# PWM_Controller_SG3525.net
KiCad netlist of a schematic drawn in Altium Designer
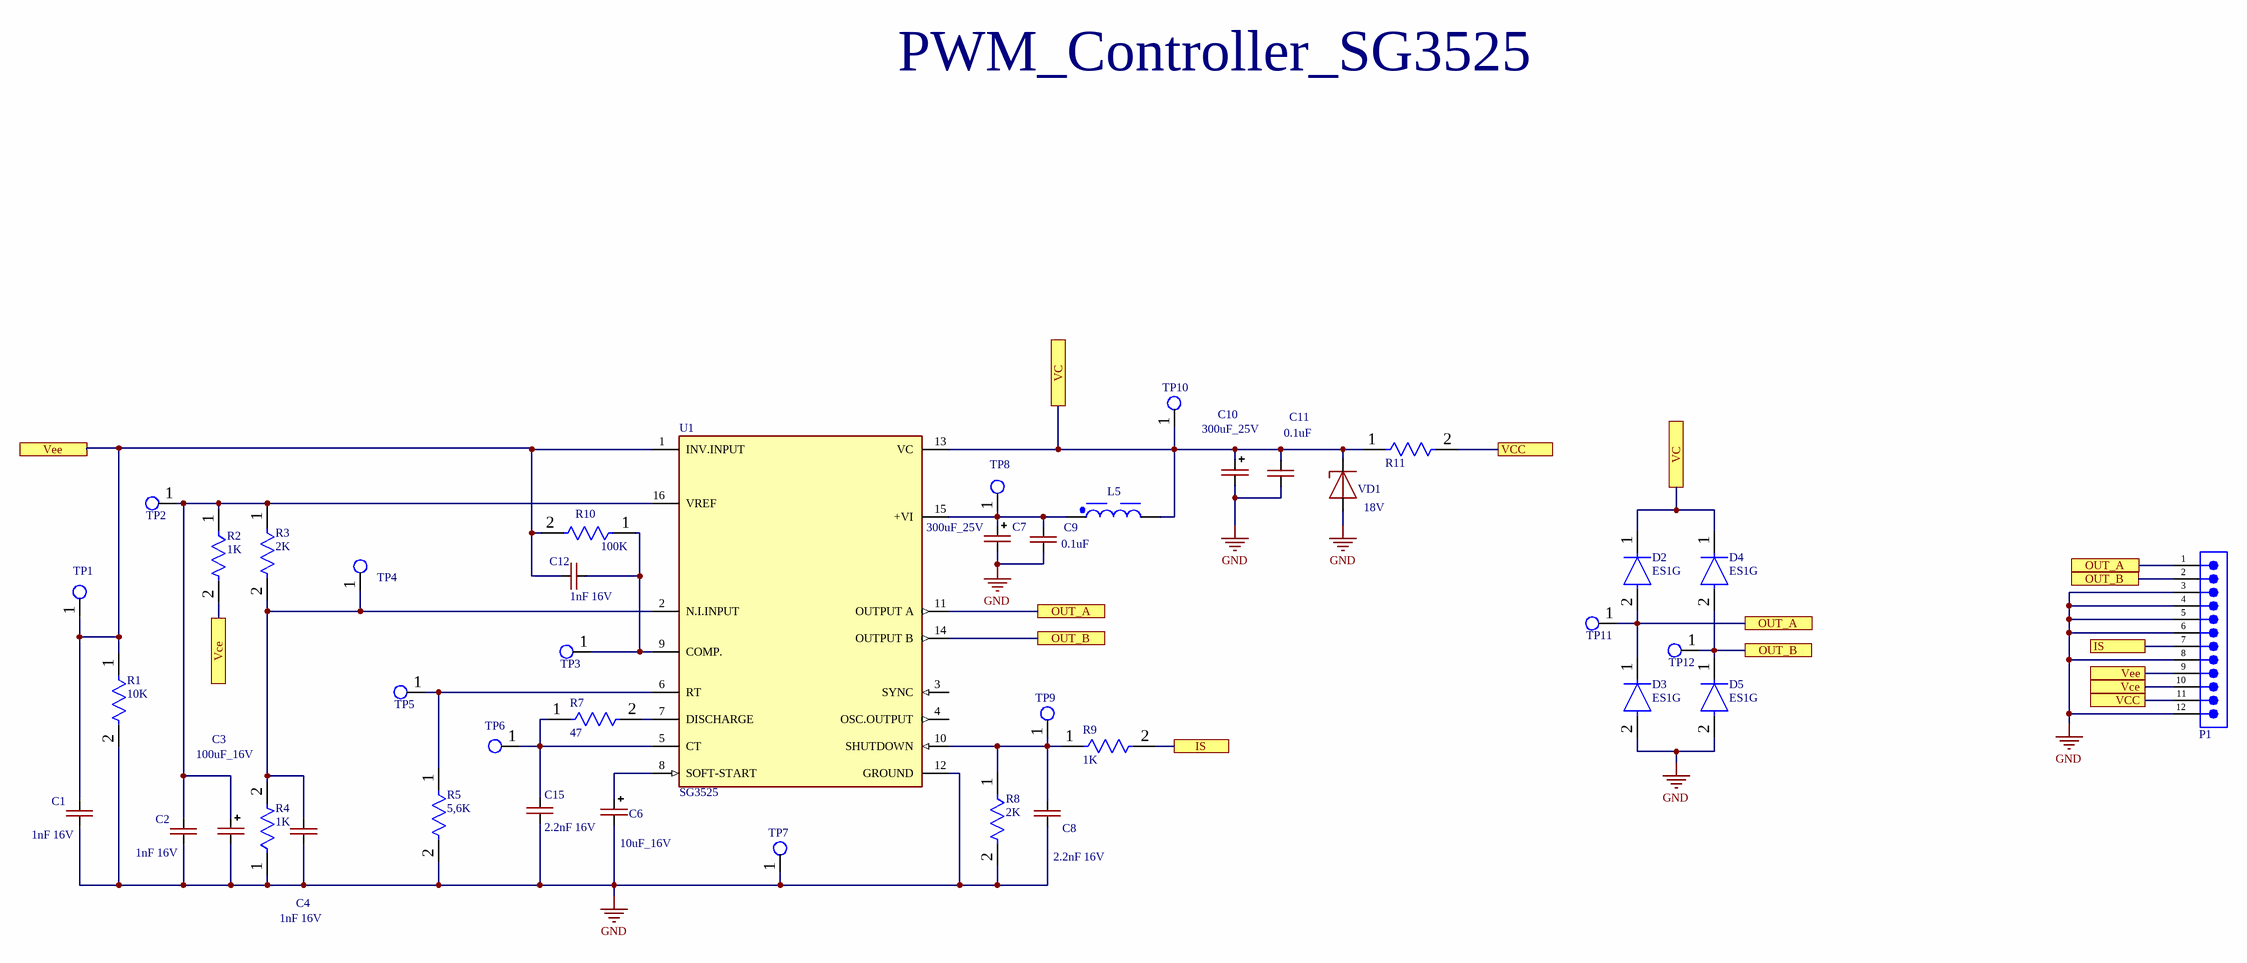
[diagram p0: PWM_Controller_SG3525.SchDoc]

(export (version "E")
  (design (tool "Eeschema 10.0.6"))
  (components
    (comp (ref "C1")
      (value "1nF 16V")
      (footprint "CAP-0805")
      (libsource (lib "PASSIVE_COMPONENTS") (part "CAP-NON-POLAR"))
    )
    (comp (ref "C2")
      (value "1nF 16V")
      (footprint "CAP-0805")
      (libsource (lib "PASSIVE_COMPONENTS") (part "CAP-NON-POLAR"))
    )
    (comp (ref "C3")
      (value "100uF_16V")
      (footprint "CAP-TAN-D")
      (libsource (lib "PASSIVE_COMPONENTS") (part "CAP-POLAR"))
    )
    (comp (ref "C4")
      (value "1nF 16V")
      (footprint "CAP-0805")
      (libsource (lib "PASSIVE_COMPONENTS") (part "CAP-NON-POLAR"))
    )
    (comp (ref "C6")
      (value "10uF_16V")
      (footprint "CAP-TAN-D")
      (libsource (lib "PASSIVE_COMPONENTS") (part "CAP-POLAR"))
    )
    (comp (ref "C7")
      (value "300uF_25V")
      (footprint "CAP_SMD_Size_G")
      (libsource (lib "PASSIVE_COMPONENTS") (part "CAP_POL_SMD"))
    )
    (comp (ref "C8")
      (value "2.2nF 16V")
      (footprint "CAP-0805")
      (libsource (lib "PASSIVE_COMPONENTS") (part "CAP-NON-POLAR"))
    )
    (comp (ref "C9")
      (value "0.1uF")
      (footprint "CAP-0805")
      (libsource (lib "PASSIVE_COMPONENTS") (part "CAP-NON-POLAR"))
    )
    (comp (ref "C10")
      (value "300uF_25V")
      (footprint "CAP_SMD_Size_G")
      (libsource (lib "PASSIVE_COMPONENTS") (part "CAP_POL_SMD"))
    )
    (comp (ref "C11")
      (value "0.1uF")
      (footprint "CAP-0805")
      (libsource (lib "PASSIVE_COMPONENTS") (part "CAP-NON-POLAR"))
    )
    (comp (ref "C12")
      (value "1nF 16V")
      (footprint "CAP-0805")
      (libsource (lib "PASSIVE_COMPONENTS") (part "CAP-NON-POLAR"))
    )
    (comp (ref "C15")
      (value "2.2nF 16V")
      (footprint "CAP-0805")
      (libsource (lib "PASSIVE_COMPONENTS") (part "CAP-NON-POLAR"))
    )
    (comp (ref "D2")
      (value "ES1G")
      (footprint "FP-403AE-MFG")
      (description "Ultrafast")
      (libsource (lib "Diodes") (part "ES1G"))
    )
    (comp (ref "D3")
      (value "ES1G")
      (footprint "FP-403AE-MFG")
      (description "Ultrafast")
      (libsource (lib "Diodes") (part "ES1G"))
    )
    (comp (ref "D4")
      (value "ES1G")
      (footprint "FP-403AE-MFG")
      (description "Ultrafast")
      (libsource (lib "Diodes") (part "ES1G"))
    )
    (comp (ref "D5")
      (value "ES1G")
      (footprint "FP-403AE-MFG")
      (description "Ultrafast")
      (libsource (lib "Diodes") (part "ES1G"))
    )
    (comp (ref "L5")
      (value "47µH, 1.17A")
      (footprint "WE-PD2_7850")
      (description "WE-PD2 SMT Power Inductor, size 7850, 47µH, 1.17A, 0.18Ω")
      (fields
        (field (name "MANUFACTURER PART NUMBER") "744775147")
        (field (name "MANUFACTURER") "Wurth Elektronik")
      )
      (libsource (lib "WE-PD2 (rev22d)") (part "744775147"))
    )
    (comp (ref "P1")
      (value "61301211021")
      (footprint "61301211021")
      (description "WR-PHD Pin Header, THT, Angled, pitch 2.54mm, 1 Row, 12P")
      (fields (field (name "MANUFACTURER") "Wurth Elektronik"))
      (libsource (lib "Altium_WR-PHD (rev22b)") (part "61301211021"))
    )
    (comp (ref "R1")
      (value "10K")
      (footprint "RES-0805")
      (libsource (lib "PASSIVE_COMPONENTS") (part "RES-CONST"))
    )
    (comp (ref "R2")
      (value "1K")
      (footprint "RES-0805")
      (libsource (lib "PASSIVE_COMPONENTS") (part "RES-CONST"))
    )
    (comp (ref "R3")
      (value "2K")
      (footprint "RES-0805")
      (libsource (lib "PASSIVE_COMPONENTS") (part "RES-CONST"))
    )
    (comp (ref "R4")
      (value "1K")
      (footprint "RES-0805")
      (libsource (lib "PASSIVE_COMPONENTS") (part "RES-CONST"))
    )
    (comp (ref "R5")
      (value "5,6K")
      (footprint "RES-0805")
      (libsource (lib "PASSIVE_COMPONENTS") (part "RES-CONST"))
    )
    (comp (ref "R7")
      (value "47")
      (footprint "RES-0805")
      (libsource (lib "PASSIVE_COMPONENTS") (part "RES-CONST"))
    )
    (comp (ref "R8")
      (value "2K")
      (footprint "RES-0805")
      (libsource (lib "PASSIVE_COMPONENTS") (part "RES-CONST"))
    )
    (comp (ref "R9")
      (value "1K")
      (footprint "RES-0805")
      (libsource (lib "PASSIVE_COMPONENTS") (part "RES-CONST"))
    )
    (comp (ref "R10")
      (value "100K")
      (footprint "RES-0805")
      (libsource (lib "PASSIVE_COMPONENTS") (part "RES-CONST"))
    )
    (comp (ref "R11")
      (value "RES_1210")
      (footprint "RES_SMD_1210_IPC_A")
      (libsource (lib "PASSIVE_COMPONENTS") (part "RES_1210"))
    )
    (comp (ref "TP1")
      (value "~")
      (footprint "Test_Point")
      (description "Test_Point")
      (libsource (lib "Connectors") (part "TP_PCB?"))
    )
    (comp (ref "TP2")
      (value "~")
      (footprint "Test_Point")
      (description "Test_Point")
      (libsource (lib "Connectors") (part "TP_PCB?"))
    )
    (comp (ref "TP3")
      (value "~")
      (footprint "Test_Point")
      (description "Test_Point")
      (libsource (lib "Connectors") (part "TP_PCB?"))
    )
    (comp (ref "TP4")
      (value "~")
      (footprint "Test_Point")
      (description "Test_Point")
      (libsource (lib "Connectors") (part "TP_PCB?"))
    )
    (comp (ref "TP5")
      (value "~")
      (footprint "Test_Point")
      (description "Test_Point")
      (libsource (lib "Connectors") (part "TP_PCB?"))
    )
    (comp (ref "TP6")
      (value "~")
      (footprint "Test_Point")
      (description "Test_Point")
      (libsource (lib "Connectors") (part "TP_PCB?"))
    )
    (comp (ref "TP7")
      (value "~")
      (footprint "Test_Point")
      (description "Test_Point")
      (libsource (lib "Connectors") (part "TP_PCB?"))
    )
    (comp (ref "TP8")
      (value "~")
      (footprint "Test_Point")
      (description "Test_Point")
      (libsource (lib "Connectors") (part "TP_PCB?"))
    )
    (comp (ref "TP9")
      (value "~")
      (footprint "Test_Point")
      (description "Test_Point")
      (libsource (lib "Connectors") (part "TP_PCB?"))
    )
    (comp (ref "TP10")
      (value "~")
      (footprint "Test_Point")
      (description "Test_Point")
      (libsource (lib "Connectors") (part "TP_PCB?"))
    )
    (comp (ref "TP11")
      (value "~")
      (footprint "Test_Point")
      (description "Test_Point")
      (libsource (lib "Connectors") (part "TP_PCB?"))
    )
    (comp (ref "TP12")
      (value "~")
      (footprint "Test_Point")
      (description "Test_Point")
      (libsource (lib "Connectors") (part "TP_PCB?"))
    )
    (comp (ref "U1")
      (value "SG3525")
      (footprint "SOIC-16-L")
      (libsource (lib "Integrated_Circuts") (part "SG3525"))
    )
    (comp (ref "VD1") (value "18V") (footprint "DO-017AA") (libsource (lib "Diodes") (part "ZENER")))
  )
  (nets
    (net (code "1") (name "/IS") (class "Default")
      (node (ref "P1") (pin "7") (pinfunction "7_7") (pintype "passive"))
      (node (ref "R9") (pin "2") (pinfunction "2_2") (pintype "passive"))
    )
    (net (code "2") (name "/OUT_A") (class "Default")
      (node (ref "D2") (pin "2") (pinfunction "A_2") (pintype "passive"))
      (node (ref "D3") (pin "1") (pinfunction "C_1") (pintype "passive"))
      (node (ref "P1") (pin "1") (pinfunction "1_1") (pintype "passive"))
      (node (ref "TP11") (pin "1") (pinfunction "G9_1") (pintype "passive"))
      (node (ref "U1") (pin "11") (pinfunction "OUTPUT_A_11") (pintype "output"))
    )
    (net (code "3") (name "/OUT_B") (class "Default")
      (node (ref "D4") (pin "2") (pinfunction "A_2") (pintype "passive"))
      (node (ref "D5") (pin "1") (pinfunction "C_1") (pintype "passive"))
      (node (ref "P1") (pin "2") (pinfunction "2_2") (pintype "passive"))
      (node (ref "TP12") (pin "1") (pinfunction "G9_1") (pintype "passive"))
      (node (ref "U1") (pin "14") (pinfunction "OUTPUT_B_14") (pintype "output"))
    )
    (net (code "4") (name "/VC") (class "Default")
      (node (ref "C10") (pin "1") (pinfunction "+_1") (pintype "passive"))
      (node (ref "C11") (pin "2") (pinfunction "2_2") (pintype "passive"))
      (node (ref "D2") (pin "1") (pinfunction "C_1") (pintype "passive"))
      (node (ref "D4") (pin "1") (pinfunction "C_1") (pintype "passive"))
      (node (ref "L5") (pin "2") (pinfunction "2_2") (pintype "passive"))
      (node (ref "R11") (pin "1") (pinfunction "1_1") (pintype "passive"))
      (node (ref "TP10") (pin "1") (pinfunction "G9_1") (pintype "passive"))
      (node (ref "U1") (pin "13") (pinfunction "VC_13") (pintype "power_in"))
      (node (ref "VD1") (pin "1") (pinfunction "C_1") (pintype "passive"))
    )
    (net (code "5") (name "/VCC") (class "Default")
      (node (ref "P1") (pin "11") (pinfunction "11_11") (pintype "passive"))
      (node (ref "R11") (pin "2") (pinfunction "2_2") (pintype "passive"))
    )
    (net (code "6") (name "/Vce") (class "Default")
      (node (ref "P1") (pin "10") (pinfunction "10_10") (pintype "passive"))
      (node (ref "R2") (pin "2") (pinfunction "2_2") (pintype "passive"))
    )
    (net (code "7") (name "/Vee") (class "Default")
      (node (ref "C1") (pin "2") (pinfunction "2_2") (pintype "passive"))
      (node (ref "C12") (pin "1") (pinfunction "1_1") (pintype "passive"))
      (node (ref "P1") (pin "9") (pinfunction "9_9") (pintype "passive"))
      (node (ref "R1") (pin "1") (pinfunction "1_1") (pintype "passive"))
      (node (ref "R10") (pin "2") (pinfunction "2_2") (pintype "passive"))
      (node (ref "TP1") (pin "1") (pinfunction "G9_1") (pintype "passive"))
      (node (ref "U1") (pin "1") (pinfunction "INV.INPUT_1") (pintype "tri_state"))
    )
    (net (code "8") (name "GND") (class "Default")
      (node (ref "C1") (pin "1") (pinfunction "1_1") (pintype "passive"))
      (node (ref "C10") (pin "2") (pinfunction "-_2") (pintype "passive"))
      (node (ref "C11") (pin "1") (pinfunction "1_1") (pintype "passive"))
      (node (ref "C15") (pin "1") (pinfunction "1_1") (pintype "passive"))
      (node (ref "C2") (pin "1") (pinfunction "1_1") (pintype "passive"))
      (node (ref "C3") (pin "2") (pinfunction "-_2") (pintype "passive"))
      (node (ref "C4") (pin "1") (pinfunction "1_1") (pintype "passive"))
      (node (ref "C6") (pin "2") (pinfunction "-_2") (pintype "passive"))
      (node (ref "C7") (pin "2") (pinfunction "-_2") (pintype "passive"))
      (node (ref "C8") (pin "1") (pinfunction "1_1") (pintype "passive"))
      (node (ref "C9") (pin "1") (pinfunction "1_1") (pintype "passive"))
      (node (ref "D3") (pin "2") (pinfunction "A_2") (pintype "passive"))
      (node (ref "D5") (pin "2") (pinfunction "A_2") (pintype "passive"))
      (node (ref "P1") (pin "12") (pinfunction "12_12") (pintype "passive"))
      (node (ref "P1") (pin "3") (pinfunction "3_3") (pintype "passive"))
      (node (ref "P1") (pin "4") (pinfunction "4_4") (pintype "passive"))
      (node (ref "P1") (pin "5") (pinfunction "5_5") (pintype "passive"))
      (node (ref "P1") (pin "6") (pinfunction "6_6") (pintype "passive"))
      (node (ref "P1") (pin "8") (pinfunction "8_8") (pintype "passive"))
      (node (ref "R1") (pin "2") (pinfunction "2_2") (pintype "passive"))
      (node (ref "R4") (pin "1") (pinfunction "1_1") (pintype "passive"))
      (node (ref "R5") (pin "2") (pinfunction "2_2") (pintype "passive"))
      (node (ref "R8") (pin "2") (pinfunction "2_2") (pintype "passive"))
      (node (ref "TP7") (pin "1") (pinfunction "G9_1") (pintype "passive"))
      (node (ref "U1") (pin "12") (pinfunction "GROUND_12") (pintype "power_in"))
      (node (ref "VD1") (pin "2") (pinfunction "A_2") (pintype "passive"))
    )
    (net (code "9") (name "Net-(C3-+)") (class "Default")
      (node (ref "C2") (pin "2") (pinfunction "2_2") (pintype "passive"))
      (node (ref "C3") (pin "1") (pinfunction "+_1") (pintype "passive"))
      (node (ref "R2") (pin "1") (pinfunction "1_1") (pintype "passive"))
      (node (ref "R3") (pin "1") (pinfunction "1_1") (pintype "passive"))
      (node (ref "TP2") (pin "1") (pinfunction "G9_1") (pintype "passive"))
      (node (ref "U1") (pin "16") (pinfunction "VREF_16") (pintype "passive"))
    )
    (net (code "10") (name "Net-(C6-+)") (class "Default")
      (node (ref "C6") (pin "1") (pinfunction "+_1") (pintype "passive"))
      (node (ref "U1") (pin "8") (pinfunction "SOFT-START_8") (pintype "input"))
    )
    (net (code "11") (name "Net-(C7-+)") (class "Default")
      (node (ref "C7") (pin "1") (pinfunction "+_1") (pintype "passive"))
      (node (ref "C9") (pin "2") (pinfunction "2_2") (pintype "passive"))
      (node (ref "L5") (pin "1") (pinfunction "1_1") (pintype "passive"))
      (node (ref "TP8") (pin "1") (pinfunction "G9_1") (pintype "passive"))
      (node (ref "U1") (pin "15") (pinfunction "+VI_15") (pintype "power_in"))
    )
    (net (code "12") (name "Net-(TP3-G9)") (class "Default")
      (node (ref "C12") (pin "2") (pinfunction "2_2") (pintype "passive"))
      (node (ref "R10") (pin "1") (pinfunction "1_1") (pintype "passive"))
      (node (ref "TP3") (pin "1") (pinfunction "G9_1") (pintype "passive"))
      (node (ref "U1") (pin "9") (pinfunction "COMP._9") (pintype "passive"))
    )
    (net (code "13") (name "Net-(TP4-G9)") (class "Default")
      (node (ref "C4") (pin "2") (pinfunction "2_2") (pintype "passive"))
      (node (ref "R3") (pin "2") (pinfunction "2_2") (pintype "passive"))
      (node (ref "R4") (pin "2") (pinfunction "2_2") (pintype "passive"))
      (node (ref "TP4") (pin "1") (pinfunction "G9_1") (pintype "passive"))
      (node (ref "U1") (pin "2") (pinfunction "N.I.INPUT_2") (pintype "tri_state"))
    )
    (net (code "14") (name "Net-(TP5-G9)") (class "Default")
      (node (ref "R5") (pin "1") (pinfunction "1_1") (pintype "passive"))
      (node (ref "TP5") (pin "1") (pinfunction "G9_1") (pintype "passive"))
      (node (ref "U1") (pin "6") (pinfunction "RT_6") (pintype "passive"))
    )
    (net (code "15") (name "Net-(TP6-G9)") (class "Default")
      (node (ref "C15") (pin "2") (pinfunction "2_2") (pintype "passive"))
      (node (ref "R7") (pin "1") (pinfunction "1_1") (pintype "passive"))
      (node (ref "TP6") (pin "1") (pinfunction "G9_1") (pintype "passive"))
      (node (ref "U1") (pin "5") (pinfunction "CT_5") (pintype "passive"))
    )
    (net (code "16") (name "Net-(TP9-G9)") (class "Default")
      (node (ref "C8") (pin "2") (pinfunction "2_2") (pintype "passive"))
      (node (ref "R8") (pin "1") (pinfunction "1_1") (pintype "passive"))
      (node (ref "R9") (pin "1") (pinfunction "1_1") (pintype "passive"))
      (node (ref "TP9") (pin "1") (pinfunction "G9_1") (pintype "passive"))
      (node (ref "U1") (pin "10") (pinfunction "SHUTDOWN_10") (pintype "input"))
    )
    (net (code "17") (name "Net-(U1-DISCHARGE)") (class "Default")
      (node (ref "R7") (pin "2") (pinfunction "2_2") (pintype "passive"))
      (node (ref "U1") (pin "7") (pinfunction "DISCHARGE_7") (pintype "passive"))
    )
    (net (code "18") (name "unconnected-(U1-OSC.OUTPUT-Pad4)") (class "Default")
      (node (ref "U1") (pin "4") (pinfunction "OSC.OUTPUT_4") (pintype "output"))
    )
    (net (code "19") (name "unconnected-(U1-SYNC-Pad3)") (class "Default")
      (node (ref "U1") (pin "3") (pinfunction "SYNC_3") (pintype "input"))
    )
  )
)
